# FTDI-Breakout_v30.net
KiCad netlist of a schematic drawn in EAGLE
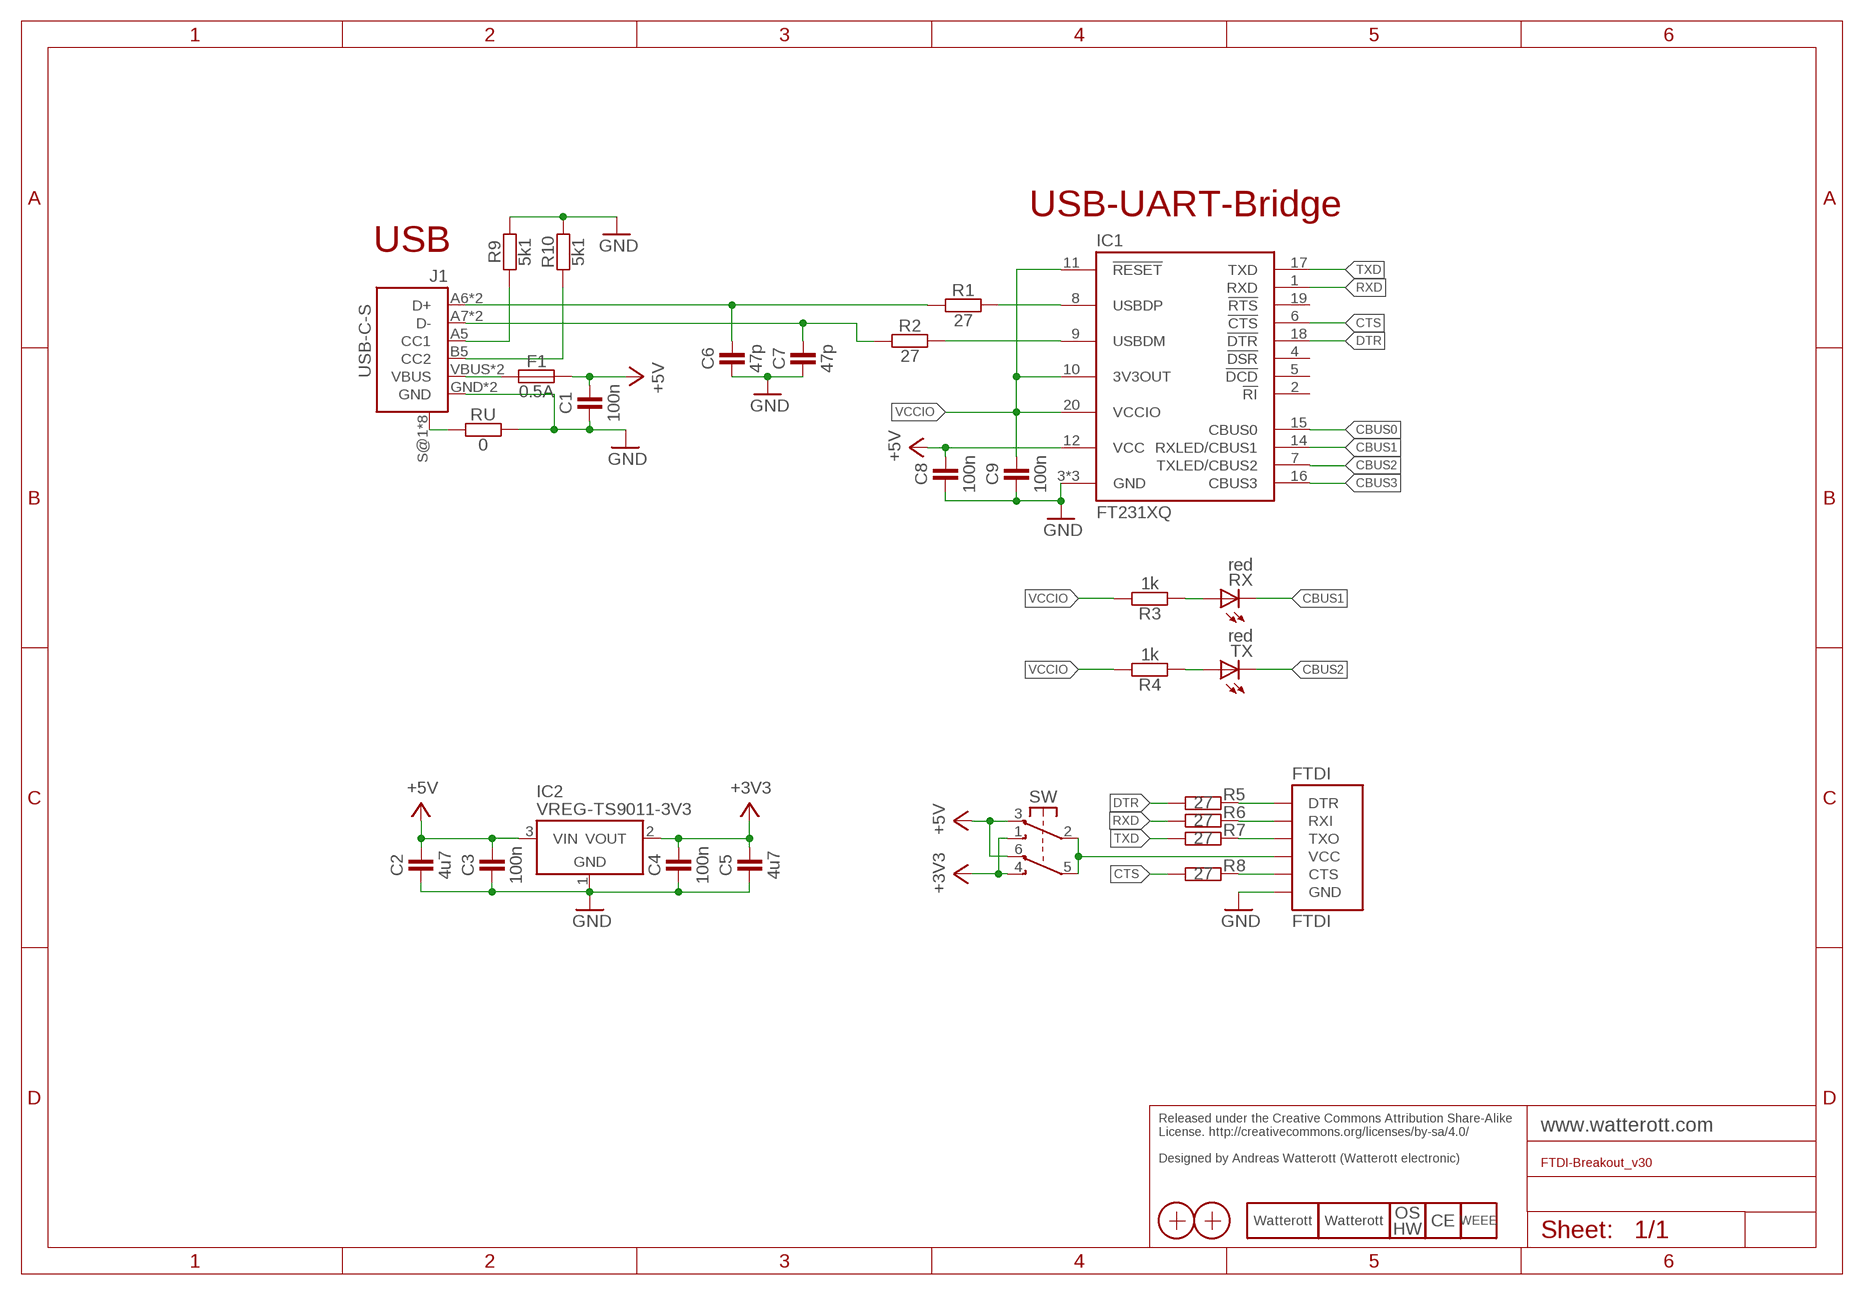
[diagram p0: schematic, sheet 1]

(export (version "E")
  (design (tool "Eeschema 10.0.6"))
  (components
    (comp (ref "C1")
      (value "100n")
      (footprint "eagle-import:C0603")
      (libsource (lib "eagle-import") (part "CAPACITOR-0603"))
    )
    (comp (ref "C2")
      (value "4u7")
      (footprint "eagle-import:C0805")
      (libsource (lib "eagle-import") (part "CAPACITOR-0805"))
    )
    (comp (ref "C3")
      (value "100n")
      (footprint "eagle-import:C0603")
      (libsource (lib "eagle-import") (part "CAPACITOR-0603"))
    )
    (comp (ref "C4")
      (value "100n")
      (footprint "eagle-import:C0603")
      (libsource (lib "eagle-import") (part "CAPACITOR-0603"))
    )
    (comp (ref "C5")
      (value "4u7")
      (footprint "eagle-import:C0805")
      (libsource (lib "eagle-import") (part "CAPACITOR-0805"))
    )
    (comp (ref "C6")
      (value "47p")
      (footprint "eagle-import:C0603")
      (libsource (lib "eagle-import") (part "CAPACITOR-0603"))
    )
    (comp (ref "C7")
      (value "47p")
      (footprint "eagle-import:C0603")
      (libsource (lib "eagle-import") (part "CAPACITOR-0603"))
    )
    (comp (ref "C8")
      (value "100n")
      (footprint "eagle-import:C0603")
      (libsource (lib "eagle-import") (part "CAPACITOR-0603"))
    )
    (comp (ref "C9")
      (value "100n")
      (footprint "eagle-import:C0603")
      (libsource (lib "eagle-import") (part "CAPACITOR-0603"))
    )
    (comp (ref "F1")
      (value "0.5A")
      (footprint "eagle-import:C0805")
      (libsource (lib "eagle-import") (part "FUSE-0805"))
    )
    (comp (ref "FTDI")
      (value "FTDI")
      (footprint "eagle-import:FTDI")
      (libsource (lib "eagle-import") (part "FTDI"))
    )
    (comp (ref "IC1")
      (value "FT231XQ")
      (footprint "eagle-import:QFN20-PAD")
      (libsource (lib "eagle-import") (part "FT231XQ"))
    )
    (comp (ref "IC2")
      (value "VREG-TS9011-3V3")
      (footprint "eagle-import:SOT23")
      (libsource (lib "eagle-import") (part "VREG-TS9011-3V3"))
    )
    (comp (ref "J1")
      (value "USB-C-S")
      (footprint "eagle-import:USB-C-S")
      (libsource (lib "eagle-import") (part "USB-C-S"))
    )
    (comp (ref "LOGO5")
      (value "LOGO_SPARK-2")
      (footprint "eagle-import:SPARK_2MM")
      (libsource (lib "eagle-import") (part "LOGO_SPARK-2"))
    )
    (comp (ref "LOGO6")
      (value "LOGO_SPARK-4")
      (footprint "eagle-import:SPARK_4MM")
      (libsource (lib "eagle-import") (part "LOGO_SPARK-4"))
    )
    (comp (ref "LOGO7")
      (value "LOGO_OSHW-2")
      (footprint "eagle-import:OSHW_2MM")
      (libsource (lib "eagle-import") (part "LOGO_OSHW-2"))
    )
    (comp (ref "LOGO8")
      (value "LOGO_CE-2")
      (footprint "eagle-import:CE_2MM")
      (libsource (lib "eagle-import") (part "LOGO_CE-2"))
    )
    (comp (ref "LOGO9")
      (value "LOGO_WEEE-4")
      (footprint "eagle-import:WEEE_4MM")
      (libsource (lib "eagle-import") (part "LOGO_WEEE-4"))
    )
    (comp (ref "R1")
      (value "27")
      (footprint "eagle-import:C0603")
      (libsource (lib "eagle-import") (part "RESISTOR-0603"))
    )
    (comp (ref "R2")
      (value "27")
      (footprint "eagle-import:C0603")
      (libsource (lib "eagle-import") (part "RESISTOR-0603"))
    )
    (comp (ref "R3")
      (value "1k")
      (footprint "eagle-import:C0603")
      (libsource (lib "eagle-import") (part "RESISTOR-0603"))
    )
    (comp (ref "R4")
      (value "1k")
      (footprint "eagle-import:C0603")
      (libsource (lib "eagle-import") (part "RESISTOR-0603"))
    )
    (comp (ref "R5")
      (value "27")
      (footprint "eagle-import:C0603")
      (libsource (lib "eagle-import") (part "RESISTOR-0603"))
    )
    (comp (ref "R6")
      (value "27")
      (footprint "eagle-import:C0603")
      (libsource (lib "eagle-import") (part "RESISTOR-0603"))
    )
    (comp (ref "R7")
      (value "27")
      (footprint "eagle-import:C0603")
      (libsource (lib "eagle-import") (part "RESISTOR-0603"))
    )
    (comp (ref "R8")
      (value "27")
      (footprint "eagle-import:C0603")
      (libsource (lib "eagle-import") (part "RESISTOR-0603"))
    )
    (comp (ref "R9")
      (value "5k1")
      (footprint "eagle-import:C0603")
      (libsource (lib "eagle-import") (part "RESISTOR-0603"))
    )
    (comp (ref "R10")
      (value "5k1")
      (footprint "eagle-import:C0603")
      (libsource (lib "eagle-import") (part "RESISTOR-0603"))
    )
    (comp (ref "RU")
      (value "0")
      (footprint "eagle-import:C0603")
      (libsource (lib "eagle-import") (part "RESISTOR-0603"))
    )
    (comp (ref "RX")
      (value "red")
      (footprint "eagle-import:C0603")
      (libsource (lib "eagle-import") (part "LED-0603"))
    )
    (comp (ref "SW")
      (value "SW-2UM-CUS22B")
      (footprint "eagle-import:CUS22B")
      (libsource (lib "eagle-import") (part "SW-2UM-CUS22B"))
    )
    (comp (ref "TX")
      (value "red")
      (footprint "eagle-import:C0603")
      (libsource (lib "eagle-import") (part "LED-0603"))
    )
    (comp (ref "X1")
      (value "PASSER-07")
      (footprint "eagle-import:PASSER_07MM")
      (libsource (lib "eagle-import") (part "PASSER-07"))
    )
    (comp (ref "X2")
      (value "PASSER-07")
      (footprint "eagle-import:PASSER_07MM")
      (libsource (lib "eagle-import") (part "PASSER-07"))
    )
  )
  (nets
    (net (code "1") (name "+3V3") (class "Default")
      (node (ref "C4") (pin "2") (pinfunction "2_2") (pintype "passive"))
      (node (ref "C5") (pin "2") (pinfunction "2_2") (pintype "passive"))
      (node (ref "IC2") (pin "2") (pinfunction "VOUT_2") (pintype "power_in"))
      (node (ref "SW") (pin "1") (pinfunction "NO1_1") (pintype "passive"))
      (node (ref "SW") (pin "4") (pinfunction "NO2_4") (pintype "passive"))
    )
    (net (code "2") (name "+5V") (class "Default")
      (node (ref "C1") (pin "2") (pinfunction "2_2") (pintype "passive"))
      (node (ref "C2") (pin "2") (pinfunction "2_2") (pintype "passive"))
      (node (ref "C3") (pin "2") (pinfunction "2_2") (pintype "passive"))
      (node (ref "C8") (pin "2") (pinfunction "2_2") (pintype "passive"))
      (node (ref "F1") (pin "2") (pinfunction "2_2") (pintype "passive"))
      (node (ref "IC1") (pin "12") (pinfunction "VCC_12") (pintype "power_in"))
      (node (ref "IC2") (pin "3") (pinfunction "VIN_3") (pintype "power_in"))
      (node (ref "SW") (pin "3") (pinfunction "NC1_3") (pintype "passive"))
      (node (ref "SW") (pin "6") (pinfunction "NC2_6") (pintype "passive"))
    )
    (net (code "3") (name "CBUS0") (class "Default")
      (node (ref "IC1") (pin "15") (pinfunction "CBUS0_15") (pintype "bidirectional"))
    )
    (net (code "4") (name "CBUS1") (class "Default")
      (node (ref "IC1") (pin "14") (pinfunction "RXLED/CBUS1_14") (pintype "bidirectional"))
      (node (ref "RX") (pin "C") (pinfunction "C_C") (pintype "passive"))
    )
    (net (code "5") (name "CBUS2") (class "Default")
      (node (ref "IC1") (pin "7") (pinfunction "TXLED/CBUS2_7") (pintype "bidirectional"))
      (node (ref "TX") (pin "C") (pinfunction "C_C") (pintype "passive"))
    )
    (net (code "6") (name "CBUS3") (class "Default")
      (node (ref "IC1") (pin "16") (pinfunction "CBUS3_16") (pintype "bidirectional"))
    )
    (net (code "7") (name "CTS") (class "Default")
      (node (ref "IC1") (pin "6") (pinfunction "~{CTS}_6") (pintype "bidirectional"))
      (node (ref "R8") (pin "1") (pinfunction "1_1") (pintype "passive"))
    )
    (net (code "8") (name "DTR") (class "Default")
      (node (ref "IC1") (pin "18") (pinfunction "~{DTR}_18") (pintype "bidirectional"))
      (node (ref "R5") (pin "1") (pinfunction "1_1") (pintype "passive"))
    )
    (net (code "9") (name "GND") (class "Default")
      (node (ref "C1") (pin "1") (pinfunction "1_1") (pintype "passive"))
      (node (ref "C2") (pin "1") (pinfunction "1_1") (pintype "passive"))
      (node (ref "C3") (pin "1") (pinfunction "1_1") (pintype "passive"))
      (node (ref "C4") (pin "1") (pinfunction "1_1") (pintype "passive"))
      (node (ref "C5") (pin "1") (pinfunction "1_1") (pintype "passive"))
      (node (ref "C6") (pin "1") (pinfunction "1_1") (pintype "passive"))
      (node (ref "C7") (pin "1") (pinfunction "1_1") (pintype "passive"))
      (node (ref "C8") (pin "1") (pinfunction "1_1") (pintype "passive"))
      (node (ref "C9") (pin "1") (pinfunction "1_1") (pintype "passive"))
      (node (ref "FTDI") (pin "1-GND") (pinfunction "GND_1-GND") (pintype "power_in"))
      (node (ref "IC1") (pin "13") (pinfunction "GND_13") (pintype "power_in"))
      (node (ref "IC1") (pin "3") (pinfunction "GND_3") (pintype "power_in"))
      (node (ref "IC1") (pin "TP") (pinfunction "GND_TP") (pintype "power_in"))
      (node (ref "IC2") (pin "1") (pinfunction "GND_1") (pintype "power_in"))
      (node (ref "J1") (pin "GND") (pinfunction "GND_GND") (pintype "power_in"))
      (node (ref "J1") (pin "GND2") (pinfunction "GND_GND2") (pintype "power_in"))
      (node (ref "R10") (pin "2") (pinfunction "2_2") (pintype "passive"))
      (node (ref "R9") (pin "2") (pinfunction "2_2") (pintype "passive"))
      (node (ref "RU") (pin "2") (pinfunction "2_2") (pintype "passive"))
    )
    (net (code "10") (name "Net-(C6-Pad2)") (class "Default")
      (node (ref "C6") (pin "2") (pinfunction "2_2") (pintype "passive"))
      (node (ref "J1") (pin "A6") (pinfunction "D+_A6") (pintype "bidirectional"))
      (node (ref "J1") (pin "B6") (pinfunction "D+_B6") (pintype "bidirectional"))
      (node (ref "R1") (pin "1") (pinfunction "1_1") (pintype "passive"))
    )
    (net (code "11") (name "Net-(C7-Pad2)") (class "Default")
      (node (ref "C7") (pin "2") (pinfunction "2_2") (pintype "passive"))
      (node (ref "J1") (pin "A7") (pinfunction "D-_A7") (pintype "bidirectional"))
      (node (ref "J1") (pin "B7") (pinfunction "D-_B7") (pintype "bidirectional"))
      (node (ref "R2") (pin "1") (pinfunction "1_1") (pintype "passive"))
    )
    (net (code "12") (name "Net-(F1-Pad1)") (class "Default")
      (node (ref "F1") (pin "1") (pinfunction "1_1") (pintype "passive"))
      (node (ref "J1") (pin "VBUS") (pinfunction "VBUS_VBUS") (pintype "power_in"))
      (node (ref "J1") (pin "VBUS2") (pinfunction "VBUS_VBUS2") (pintype "power_in"))
    )
    (net (code "13") (name "Net-(FTDI-CTS)") (class "Default")
      (node (ref "FTDI") (pin "2-CTS") (pinfunction "CTS_2-CTS") (pintype "bidirectional"))
      (node (ref "R8") (pin "2") (pinfunction "2_2") (pintype "passive"))
    )
    (net (code "14") (name "Net-(FTDI-DTR)") (class "Default")
      (node (ref "FTDI") (pin "6-DTR") (pinfunction "DTR_6-DTR") (pintype "bidirectional"))
      (node (ref "R5") (pin "2") (pinfunction "2_2") (pintype "passive"))
    )
    (net (code "15") (name "Net-(FTDI-RXI)") (class "Default")
      (node (ref "FTDI") (pin "5-RXI") (pinfunction "RXI_5-RXI") (pintype "bidirectional"))
      (node (ref "R6") (pin "2") (pinfunction "2_2") (pintype "passive"))
    )
    (net (code "16") (name "Net-(FTDI-TXO)") (class "Default")
      (node (ref "FTDI") (pin "4-TXO") (pinfunction "TXO_4-TXO") (pintype "bidirectional"))
      (node (ref "R7") (pin "2") (pinfunction "2_2") (pintype "passive"))
    )
    (net (code "17") (name "Net-(FTDI-VCC)") (class "Default")
      (node (ref "FTDI") (pin "3-VCC") (pinfunction "VCC_3-VCC") (pintype "power_in"))
      (node (ref "SW") (pin "2") (pinfunction "C1_2") (pintype "passive"))
      (node (ref "SW") (pin "5") (pinfunction "C2_5") (pintype "passive"))
    )
    (net (code "18") (name "Net-(IC1-USBDM)") (class "Default")
      (node (ref "IC1") (pin "9") (pinfunction "USBDM_9") (pintype "bidirectional"))
      (node (ref "R2") (pin "2") (pinfunction "2_2") (pintype "passive"))
    )
    (net (code "19") (name "Net-(IC1-USBDP)") (class "Default")
      (node (ref "IC1") (pin "8") (pinfunction "USBDP_8") (pintype "bidirectional"))
      (node (ref "R1") (pin "2") (pinfunction "2_2") (pintype "passive"))
    )
    (net (code "20") (name "Net-(J1-CC1)") (class "Default")
      (node (ref "J1") (pin "A5") (pinfunction "CC1_A5") (pintype "bidirectional"))
      (node (ref "R9") (pin "1") (pinfunction "1_1") (pintype "passive"))
    )
    (net (code "21") (name "Net-(J1-CC2)") (class "Default")
      (node (ref "J1") (pin "B5") (pinfunction "CC2_B5") (pintype "bidirectional"))
      (node (ref "R10") (pin "1") (pinfunction "1_1") (pintype "passive"))
    )
    (net (code "22") (name "Net-(J1-SHIELD-PadS@1)") (class "Default")
      (node (ref "J1") (pin "S@1") (pinfunction "SHIELD_S@1") (pintype "passive"))
      (node (ref "J1") (pin "S@2") (pinfunction "SHIELD_S@2") (pintype "passive"))
      (node (ref "J1") (pin "S@3") (pinfunction "SHIELD_S@3") (pintype "passive"))
      (node (ref "J1") (pin "S@4") (pinfunction "SHIELD_S@4") (pintype "passive"))
      (node (ref "J1") (pin "S@5") (pinfunction "SHIELD_S@5") (pintype "passive"))
      (node (ref "J1") (pin "S@6") (pinfunction "SHIELD_S@6") (pintype "passive"))
      (node (ref "J1") (pin "S@7") (pinfunction "SHIELD_S@7") (pintype "passive"))
      (node (ref "J1") (pin "S@8") (pinfunction "SHIELD_S@8") (pintype "passive"))
      (node (ref "RU") (pin "1") (pinfunction "1_1") (pintype "passive"))
    )
    (net (code "23") (name "Net-(R3-Pad1)") (class "Default")
      (node (ref "R3") (pin "1") (pinfunction "1_1") (pintype "passive"))
      (node (ref "RX") (pin "A") (pinfunction "A_A") (pintype "passive"))
    )
    (net (code "24") (name "Net-(R4-Pad1)") (class "Default")
      (node (ref "R4") (pin "1") (pinfunction "1_1") (pintype "passive"))
      (node (ref "TX") (pin "A") (pinfunction "A_A") (pintype "passive"))
    )
    (net (code "25") (name "RXD") (class "Default")
      (node (ref "IC1") (pin "1") (pinfunction "RXD_1") (pintype "bidirectional"))
      (node (ref "R6") (pin "1") (pinfunction "1_1") (pintype "passive"))
    )
    (net (code "26") (name "TXD") (class "Default")
      (node (ref "IC1") (pin "17") (pinfunction "TXD_17") (pintype "bidirectional"))
      (node (ref "R7") (pin "1") (pinfunction "1_1") (pintype "passive"))
    )
    (net (code "27") (name "VCCIO") (class "Default")
      (node (ref "C9") (pin "2") (pinfunction "2_2") (pintype "passive"))
      (node (ref "IC1") (pin "10") (pinfunction "3V3OUT_10") (pintype "power_in"))
      (node (ref "IC1") (pin "11") (pinfunction "~{RESET}_11") (pintype "bidirectional"))
      (node (ref "IC1") (pin "20") (pinfunction "VCCIO_20") (pintype "power_in"))
      (node (ref "R3") (pin "2") (pinfunction "2_2") (pintype "passive"))
      (node (ref "R4") (pin "2") (pinfunction "2_2") (pintype "passive"))
    )
    (net (code "28") (name "unconnected-(IC1-~{DCD}-Pad5)") (class "Default")
      (node (ref "IC1") (pin "5") (pinfunction "~{DCD}_5") (pintype "bidirectional"))
    )
    (net (code "29") (name "unconnected-(IC1-~{DSR}-Pad4)") (class "Default")
      (node (ref "IC1") (pin "4") (pinfunction "~{DSR}_4") (pintype "bidirectional"))
    )
    (net (code "30") (name "unconnected-(IC1-~{RI}-Pad2)") (class "Default")
      (node (ref "IC1") (pin "2") (pinfunction "~{RI}_2") (pintype "bidirectional"))
    )
    (net (code "31") (name "unconnected-(IC1-~{RTS}-Pad19)") (class "Default")
      (node (ref "IC1") (pin "19") (pinfunction "~{RTS}_19") (pintype "bidirectional"))
    )
  )
)
